# BlueCore_TM_3-Multuimedia.net
KiCad netlist of a schematic drawn in EAGLE
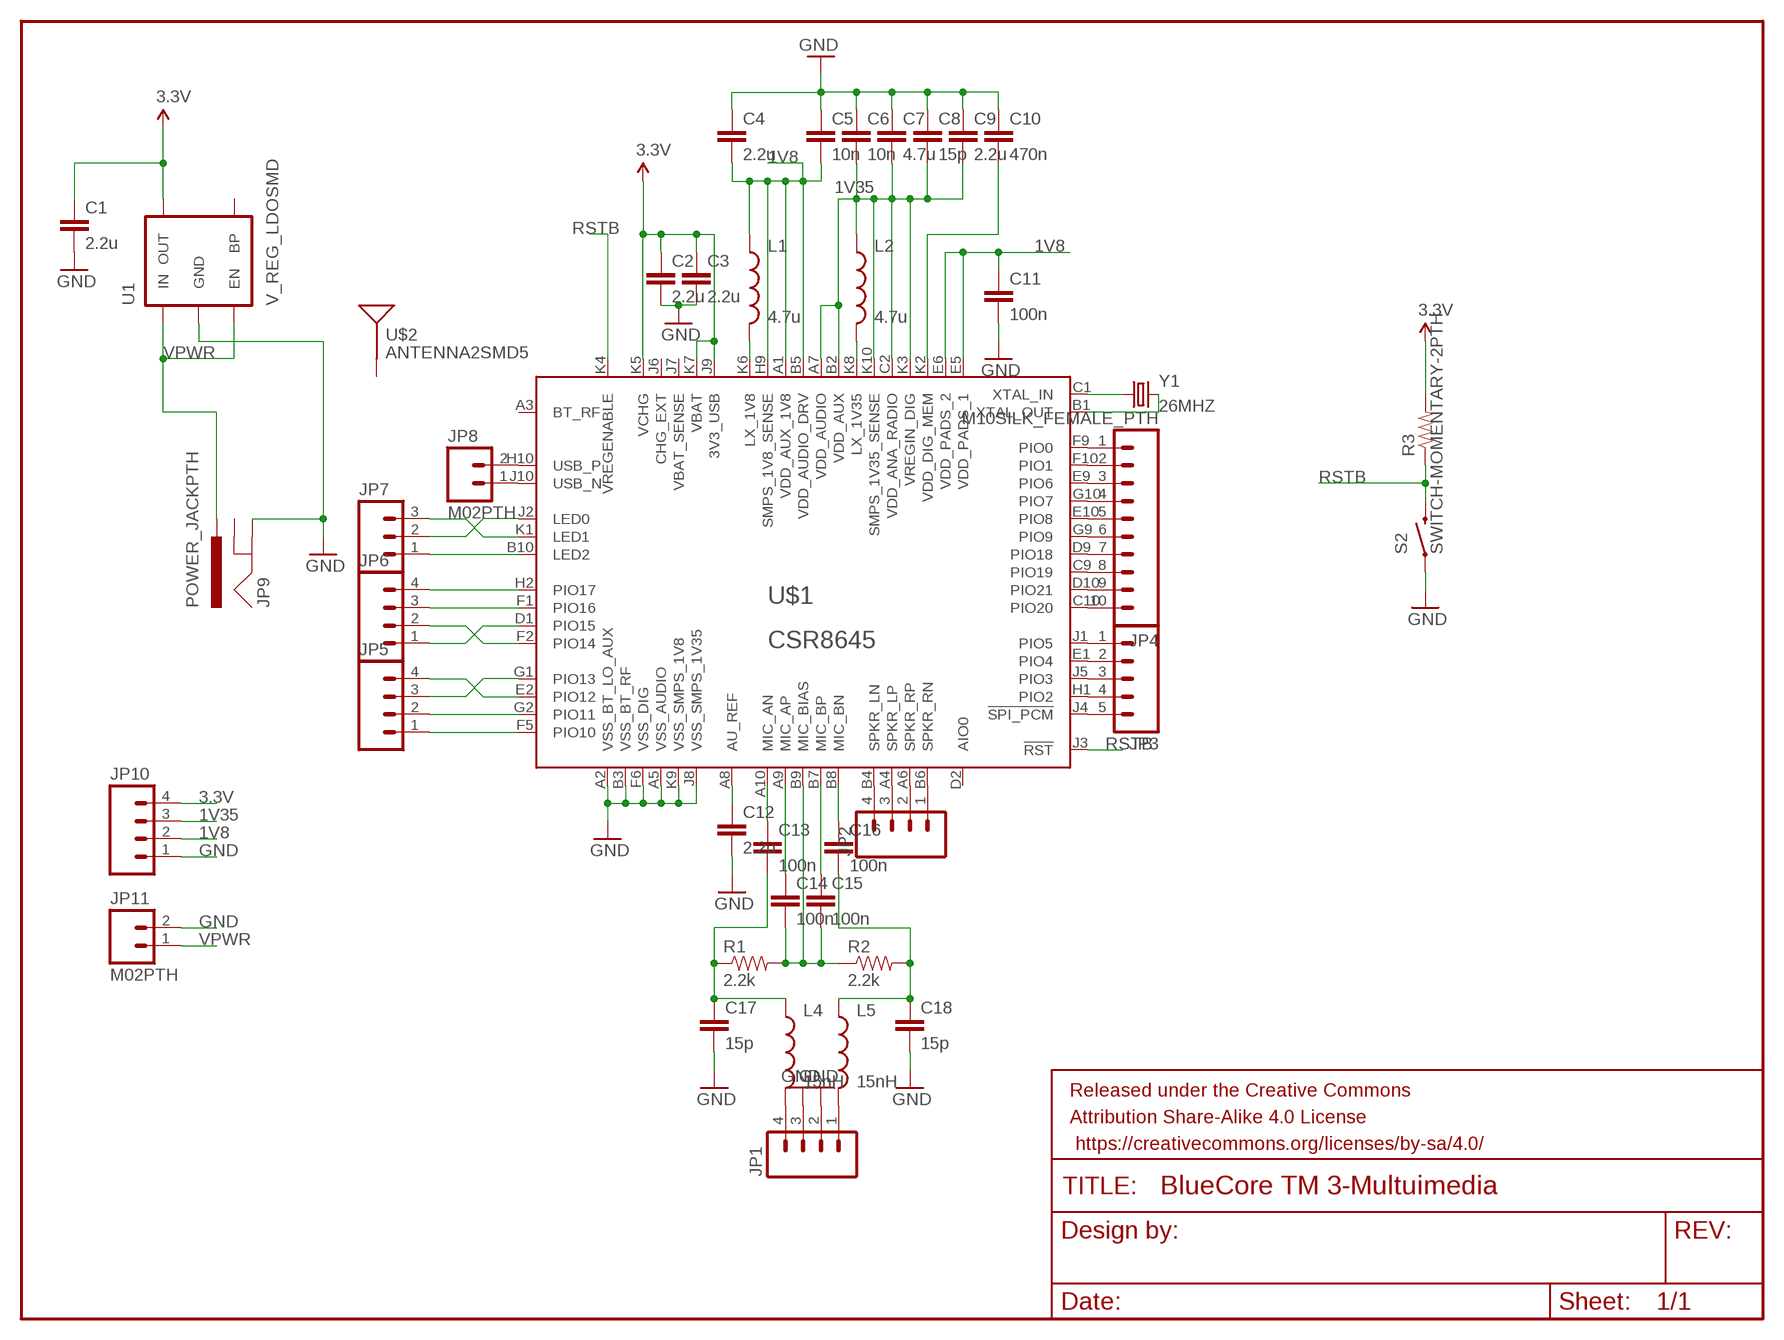
[diagram p0: schematic, sheet 1]

(export (version "E")
  (design (tool "Eeschema 10.0.6"))
  (components
    (comp (ref "C1")
      (value "2.2u")
      (footprint "eagle-import:CAP-PTH-SMALL")
      (libsource (lib "eagle-import") (part "CAPPTH"))
    )
    (comp (ref "C2")
      (value "2.2u")
      (footprint "eagle-import:CAP-PTH-SMALL")
      (libsource (lib "eagle-import") (part "CAPPTH"))
    )
    (comp (ref "C3")
      (value "2.2u")
      (footprint "eagle-import:CAP-PTH-SMALL")
      (libsource (lib "eagle-import") (part "CAPPTH"))
    )
    (comp (ref "C4")
      (value "2.2u")
      (footprint "eagle-import:CAP-PTH-SMALL")
      (libsource (lib "eagle-import") (part "CAPPTH"))
    )
    (comp (ref "C5")
      (value "10n")
      (footprint "eagle-import:CAP-PTH-SMALL")
      (libsource (lib "eagle-import") (part "CAPPTH"))
    )
    (comp (ref "C6")
      (value "10n")
      (footprint "eagle-import:CAP-PTH-SMALL")
      (libsource (lib "eagle-import") (part "CAPPTH"))
    )
    (comp (ref "C7")
      (value "4.7u")
      (footprint "eagle-import:CAP-PTH-SMALL")
      (libsource (lib "eagle-import") (part "CAPPTH"))
    )
    (comp (ref "C8")
      (value "15p")
      (footprint "eagle-import:CAP-PTH-SMALL")
      (libsource (lib "eagle-import") (part "CAPPTH"))
    )
    (comp (ref "C9")
      (value "2.2u")
      (footprint "eagle-import:CAP-PTH-SMALL")
      (libsource (lib "eagle-import") (part "CAPPTH"))
    )
    (comp (ref "C10")
      (value "470n")
      (footprint "eagle-import:CAP-PTH-SMALL")
      (libsource (lib "eagle-import") (part "CAPPTH"))
    )
    (comp (ref "C11")
      (value "100n")
      (footprint "eagle-import:CAP-PTH-SMALL")
      (libsource (lib "eagle-import") (part "CAPPTH"))
    )
    (comp (ref "C12")
      (value "2.2u")
      (footprint "eagle-import:CAP-PTH-SMALL")
      (libsource (lib "eagle-import") (part "CAPPTH"))
    )
    (comp (ref "C13")
      (value "100n")
      (footprint "eagle-import:CAP-PTH-SMALL")
      (libsource (lib "eagle-import") (part "CAPPTH"))
    )
    (comp (ref "C14")
      (value "100n")
      (footprint "eagle-import:CAP-PTH-SMALL")
      (libsource (lib "eagle-import") (part "CAPPTH"))
    )
    (comp (ref "C15")
      (value "100n")
      (footprint "eagle-import:CAP-PTH-SMALL")
      (libsource (lib "eagle-import") (part "CAPPTH"))
    )
    (comp (ref "C16")
      (value "100n")
      (footprint "eagle-import:CAP-PTH-SMALL")
      (libsource (lib "eagle-import") (part "CAPPTH"))
    )
    (comp (ref "C17")
      (value "15p")
      (footprint "eagle-import:CAP-PTH-SMALL")
      (libsource (lib "eagle-import") (part "CAPPTH"))
    )
    (comp (ref "C18")
      (value "15p")
      (footprint "eagle-import:CAP-PTH-SMALL")
      (libsource (lib "eagle-import") (part "CAPPTH"))
    )
    (comp (ref "FRAME1")
      (value "FRAME-LETTER")
      (footprint "eagle-import:CREATIVE_COMMONS")
      (libsource (lib "eagle-import") (part "FRAME-LETTER"))
    )
    (comp (ref "JP1")
      (value "M04PTH")
      (footprint "eagle-import:1X04")
      (libsource (lib "eagle-import") (part "M04PTH"))
    )
    (comp (ref "JP2")
      (value "M04PTH")
      (footprint "eagle-import:1X04")
      (libsource (lib "eagle-import") (part "M04PTH"))
    )
    (comp (ref "JP3")
      (value "M05PTH")
      (footprint "eagle-import:1X05")
      (libsource (lib "eagle-import") (part "M05PTH"))
    )
    (comp (ref "JP4")
      (value "M10SILK_FEMALE_PTH")
      (footprint "eagle-import:1X10")
      (libsource (lib "eagle-import") (part "M10SILK_FEMALE_PTH"))
    )
    (comp (ref "JP5")
      (value "M04PTH")
      (footprint "eagle-import:1X04")
      (libsource (lib "eagle-import") (part "M04PTH"))
    )
    (comp (ref "JP6")
      (value "M04PTH")
      (footprint "eagle-import:1X04")
      (libsource (lib "eagle-import") (part "M04PTH"))
    )
    (comp (ref "JP7")
      (value "M03PTH")
      (footprint "eagle-import:1X03")
      (libsource (lib "eagle-import") (part "M03PTH"))
    )
    (comp (ref "JP8")
      (value "M02PTH")
      (footprint "eagle-import:1X02")
      (libsource (lib "eagle-import") (part "M02PTH"))
    )
    (comp (ref "JP9")
      (value "POWER_JACKPTH")
      (footprint "eagle-import:POWER_JACK_PTH")
      (libsource (lib "eagle-import") (part "POWER_JACKPTH"))
    )
    (comp (ref "JP10")
      (value "M04PTH")
      (footprint "eagle-import:1X04")
      (libsource (lib "eagle-import") (part "M04PTH"))
    )
    (comp (ref "JP11")
      (value "M02PTH")
      (footprint "eagle-import:1X02")
      (libsource (lib "eagle-import") (part "M02PTH"))
    )
    (comp (ref "L1")
      (value "4.7u")
      (footprint "eagle-import:0805")
      (libsource (lib "eagle-import") (part "INDUCTOR0805"))
    )
    (comp (ref "L2")
      (value "4.7u")
      (footprint "eagle-import:0805")
      (libsource (lib "eagle-import") (part "INDUCTOR0805"))
    )
    (comp (ref "L4")
      (value "15nH")
      (footprint "eagle-import:0805")
      (libsource (lib "eagle-import") (part "INDUCTOR0805"))
    )
    (comp (ref "L5")
      (value "15nH")
      (footprint "eagle-import:0805")
      (libsource (lib "eagle-import") (part "INDUCTOR0805"))
    )
    (comp (ref "R1")
      (value "2.2k")
      (footprint "eagle-import:0805")
      (libsource (lib "eagle-import") (part "RESISTOR0805-RES"))
    )
    (comp (ref "R2")
      (value "2.2k")
      (footprint "eagle-import:0805")
      (libsource (lib "eagle-import") (part "RESISTOR0805-RES"))
    )
    (comp (ref "R3")
      (value "RESISTOR0805-RES")
      (footprint "eagle-import:0805")
      (libsource (lib "eagle-import") (part "RESISTOR0805-RES"))
    )
    (comp (ref "S2")
      (value "SWITCH-MOMENTARY-2PTH")
      (footprint "eagle-import:TACTILE-PTH")
      (libsource (lib "eagle-import") (part "SWITCH-MOMENTARY-2PTH"))
    )
    (comp (ref "U$1")
      (value "CSR8645")
      (footprint "eagle-import:VFBGA68")
      (libsource (lib "eagle-import") (part "CSR8645"))
    )
    (comp (ref "U$2")
      (value "ANTENNA2SMD5")
      (footprint "eagle-import:ANTENNA-CHIP5")
      (libsource (lib "eagle-import") (part "ANTENNA2SMD5"))
    )
    (comp (ref "U1")
      (value "V_REG_LDOSMD")
      (footprint "eagle-import:SOT23-5")
      (libsource (lib "eagle-import") (part "V_REG_LDOSMD"))
    )
    (comp (ref "Y1")
      (value "26MHZ")
      (footprint "eagle-import:HC49US")
      (libsource (lib "eagle-import") (part "CRYSTALHC49US"))
    )
  )
  (nets
    (net (code "1") (name "/1V8") (class "Default")
      (node (ref "C11") (pin "1") (pinfunction "1_1") (pintype "passive"))
      (node (ref "C4") (pin "2") (pinfunction "2_2") (pintype "passive"))
      (node (ref "C5") (pin "2") (pinfunction "2_2") (pintype "passive"))
      (node (ref "JP10") (pin "2") (pinfunction "2_2") (pintype "passive"))
      (node (ref "L1") (pin "1") (pinfunction "1_1") (pintype "passive"))
      (node (ref "U$1") (pin "A1") (pinfunction "VDD_AUX_1V8_A1") (pintype "bidirectional"))
      (node (ref "U$1") (pin "B5") (pinfunction "VDD_AUDIO_DRV_B5") (pintype "bidirectional"))
      (node (ref "U$1") (pin "E5") (pinfunction "VDD_PADS_1_E5") (pintype "bidirectional"))
      (node (ref "U$1") (pin "E6") (pinfunction "VDD_PADS_2_E6") (pintype "bidirectional"))
      (node (ref "U$1") (pin "H9") (pinfunction "SMPS_1V8_SENSE_H9") (pintype "bidirectional"))
    )
    (net (code "2") (name "/1V35") (class "Default")
      (node (ref "C6") (pin "2") (pinfunction "2_2") (pintype "passive"))
      (node (ref "C7") (pin "2") (pinfunction "2_2") (pintype "passive"))
      (node (ref "C8") (pin "2") (pinfunction "2_2") (pintype "passive"))
      (node (ref "C9") (pin "2") (pinfunction "2_2") (pintype "passive"))
      (node (ref "JP10") (pin "3") (pinfunction "3_3") (pintype "passive"))
      (node (ref "L2") (pin "1") (pinfunction "1_1") (pintype "passive"))
      (node (ref "U$1") (pin "A7") (pinfunction "VDD_AUDIO_A7") (pintype "bidirectional"))
      (node (ref "U$1") (pin "B2") (pinfunction "VDD_AUX_B2") (pintype "bidirectional"))
      (node (ref "U$1") (pin "C2") (pinfunction "VDD_ANA_RADIO_C2") (pintype "bidirectional"))
      (node (ref "U$1") (pin "K10") (pinfunction "SMPS_1V35_SENSE_K10") (pintype "bidirectional"))
      (node (ref "U$1") (pin "K3") (pinfunction "VREGIN_DIG_K3") (pintype "bidirectional"))
    )
    (net (code "3") (name "/RSTB") (class "Default")
      (node (ref "R3") (pin "1") (pinfunction "1_1") (pintype "passive"))
      (node (ref "S2") (pin "3") (pinfunction "2_3") (pintype "passive"))
      (node (ref "U$1") (pin "J3") (pinfunction "~{RST}_J3") (pintype "input"))
      (node (ref "U$1") (pin "K4") (pinfunction "VREGENABLE_K4") (pintype "bidirectional"))
    )
    (net (code "4") (name "/VPWR") (class "Default")
      (node (ref "JP11") (pin "1") (pinfunction "1_1") (pintype "passive"))
      (node (ref "JP9") (pin "PWR") (pinfunction "PWR_PWR") (pintype "bidirectional"))
      (node (ref "U1") (pin "1") (pinfunction "IN_1") (pintype "input"))
      (node (ref "U1") (pin "3") (pinfunction "EN_3") (pintype "input"))
    )
    (net (code "5") (name "3.3V") (class "Default")
      (node (ref "C1") (pin "1") (pinfunction "1_1") (pintype "passive"))
      (node (ref "C2") (pin "1") (pinfunction "1_1") (pintype "passive"))
      (node (ref "C3") (pin "1") (pinfunction "1_1") (pintype "passive"))
      (node (ref "JP10") (pin "4") (pinfunction "4_4") (pintype "passive"))
      (node (ref "R3") (pin "2") (pinfunction "2_2") (pintype "passive"))
      (node (ref "U$1") (pin "J9") (pinfunction "3V3_USB_J9") (pintype "power_in"))
      (node (ref "U$1") (pin "K5") (pinfunction "VCHG_K5") (pintype "power_in"))
      (node (ref "U$1") (pin "K7") (pinfunction "VBAT_K7") (pintype "power_in"))
      (node (ref "U1") (pin "5") (pinfunction "OUT_5") (pintype "passive"))
    )
    (net (code "6") (name "GND") (class "Default")
      (node (ref "C1") (pin "2") (pinfunction "2_2") (pintype "passive"))
      (node (ref "C10") (pin "1") (pinfunction "1_1") (pintype "passive"))
      (node (ref "C11") (pin "2") (pinfunction "2_2") (pintype "passive"))
      (node (ref "C12") (pin "2") (pinfunction "2_2") (pintype "passive"))
      (node (ref "C17") (pin "2") (pinfunction "2_2") (pintype "passive"))
      (node (ref "C18") (pin "2") (pinfunction "2_2") (pintype "passive"))
      (node (ref "C2") (pin "2") (pinfunction "2_2") (pintype "passive"))
      (node (ref "C3") (pin "2") (pinfunction "2_2") (pintype "passive"))
      (node (ref "C4") (pin "1") (pinfunction "1_1") (pintype "passive"))
      (node (ref "C5") (pin "1") (pinfunction "1_1") (pintype "passive"))
      (node (ref "C6") (pin "1") (pinfunction "1_1") (pintype "passive"))
      (node (ref "C7") (pin "1") (pinfunction "1_1") (pintype "passive"))
      (node (ref "C8") (pin "1") (pinfunction "1_1") (pintype "passive"))
      (node (ref "C9") (pin "1") (pinfunction "1_1") (pintype "passive"))
      (node (ref "JP1") (pin "2") (pinfunction "2_2") (pintype "passive"))
      (node (ref "JP1") (pin "3") (pinfunction "3_3") (pintype "passive"))
      (node (ref "JP10") (pin "1") (pinfunction "1_1") (pintype "passive"))
      (node (ref "JP11") (pin "2") (pinfunction "2_2") (pintype "passive"))
      (node (ref "JP9") (pin "GND") (pinfunction "GND_GND") (pintype "bidirectional"))
      (node (ref "S2") (pin "1") (pinfunction "1_1") (pintype "passive"))
      (node (ref "U$1") (pin "A2") (pinfunction "VSS_BT_LO_AUX_A2") (pintype "bidirectional"))
      (node (ref "U$1") (pin "A5") (pinfunction "VSS_AUDIO_A5") (pintype "bidirectional"))
      (node (ref "U$1") (pin "B3") (pinfunction "VSS_BT_RF_B3") (pintype "bidirectional"))
      (node (ref "U$1") (pin "F6") (pinfunction "VSS_DIG_F6") (pintype "bidirectional"))
      (node (ref "U$1") (pin "J8") (pinfunction "VSS_SMPS_1V35_J8") (pintype "bidirectional"))
      (node (ref "U$1") (pin "K9") (pinfunction "VSS_SMPS_1V8_K9") (pintype "bidirectional"))
      (node (ref "U1") (pin "2") (pinfunction "GND_2") (pintype "input"))
    )
    (net (code "7") (name "Net-(C13-Pad2)") (class "Default")
      (node (ref "C13") (pin "2") (pinfunction "2_2") (pintype "passive"))
      (node (ref "C17") (pin "1") (pinfunction "1_1") (pintype "passive"))
      (node (ref "L4") (pin "1") (pinfunction "1_1") (pintype "passive"))
      (node (ref "R1") (pin "1") (pinfunction "1_1") (pintype "passive"))
    )
    (net (code "8") (name "Net-(C16-Pad2)") (class "Default")
      (node (ref "C16") (pin "2") (pinfunction "2_2") (pintype "passive"))
      (node (ref "C18") (pin "1") (pinfunction "1_1") (pintype "passive"))
      (node (ref "L5") (pin "1") (pinfunction "1_1") (pintype "passive"))
      (node (ref "R2") (pin "2") (pinfunction "2_2") (pintype "passive"))
    )
    (net (code "9") (name "Net-(JP1-Pad1)") (class "Default")
      (node (ref "JP1") (pin "1") (pinfunction "1_1") (pintype "passive"))
      (node (ref "L5") (pin "2") (pinfunction "2_2") (pintype "passive"))
    )
    (net (code "10") (name "Net-(JP1-Pad4)") (class "Default")
      (node (ref "JP1") (pin "4") (pinfunction "4_4") (pintype "passive"))
      (node (ref "L4") (pin "2") (pinfunction "2_2") (pintype "passive"))
    )
    (net (code "11") (name "Net-(U$1-AU_REF)") (class "Default")
      (node (ref "C12") (pin "1") (pinfunction "1_1") (pintype "passive"))
      (node (ref "U$1") (pin "A8") (pinfunction "AU_REF_A8") (pintype "input"))
    )
    (net (code "12") (name "Net-(U$1-LED0)") (class "Default")
      (node (ref "JP7") (pin "2") (pinfunction "2_2") (pintype "passive"))
      (node (ref "U$1") (pin "J2") (pinfunction "LED0_J2") (pintype "bidirectional"))
    )
    (net (code "13") (name "Net-(U$1-LED1)") (class "Default")
      (node (ref "JP7") (pin "3") (pinfunction "3_3") (pintype "passive"))
      (node (ref "U$1") (pin "K1") (pinfunction "LED1_K1") (pintype "bidirectional"))
    )
    (net (code "14") (name "Net-(U$1-LED2)") (class "Default")
      (node (ref "JP7") (pin "1") (pinfunction "1_1") (pintype "passive"))
      (node (ref "U$1") (pin "B10") (pinfunction "LED2_B10") (pintype "bidirectional"))
    )
    (net (code "15") (name "Net-(U$1-LX_1V8)") (class "Default")
      (node (ref "L1") (pin "2") (pinfunction "2_2") (pintype "passive"))
      (node (ref "U$1") (pin "K6") (pinfunction "LX_1V8_K6") (pintype "bidirectional"))
    )
    (net (code "16") (name "Net-(U$1-LX_1V35)") (class "Default")
      (node (ref "L2") (pin "2") (pinfunction "2_2") (pintype "passive"))
      (node (ref "U$1") (pin "K8") (pinfunction "LX_1V35_K8") (pintype "bidirectional"))
    )
    (net (code "17") (name "Net-(U$1-MIC_AN)") (class "Default")
      (node (ref "C13") (pin "1") (pinfunction "1_1") (pintype "passive"))
      (node (ref "U$1") (pin "A10") (pinfunction "MIC_AN_A10") (pintype "input"))
    )
    (net (code "18") (name "Net-(U$1-MIC_AP)") (class "Default")
      (node (ref "C14") (pin "1") (pinfunction "1_1") (pintype "passive"))
      (node (ref "U$1") (pin "A9") (pinfunction "MIC_AP_A9") (pintype "input"))
    )
    (net (code "19") (name "Net-(U$1-MIC_BIAS)") (class "Default")
      (node (ref "C14") (pin "2") (pinfunction "2_2") (pintype "passive"))
      (node (ref "C15") (pin "2") (pinfunction "2_2") (pintype "passive"))
      (node (ref "R1") (pin "2") (pinfunction "2_2") (pintype "passive"))
      (node (ref "R2") (pin "1") (pinfunction "1_1") (pintype "passive"))
      (node (ref "U$1") (pin "B9") (pinfunction "MIC_BIAS_B9") (pintype "output"))
    )
    (net (code "20") (name "Net-(U$1-MIC_BN)") (class "Default")
      (node (ref "C16") (pin "1") (pinfunction "1_1") (pintype "passive"))
      (node (ref "U$1") (pin "B8") (pinfunction "MIC_BN_B8") (pintype "input"))
    )
    (net (code "21") (name "Net-(U$1-MIC_BP)") (class "Default")
      (node (ref "C15") (pin "1") (pinfunction "1_1") (pintype "passive"))
      (node (ref "U$1") (pin "B7") (pinfunction "MIC_BP_B7") (pintype "input"))
    )
    (net (code "22") (name "Net-(U$1-PIO0)") (class "Default")
      (node (ref "JP4") (pin "1") (pinfunction "1_1") (pintype "passive"))
      (node (ref "U$1") (pin "F9") (pinfunction "PIO0_F9") (pintype "bidirectional"))
    )
    (net (code "23") (name "Net-(U$1-PIO1)") (class "Default")
      (node (ref "JP4") (pin "2") (pinfunction "2_2") (pintype "passive"))
      (node (ref "U$1") (pin "F10") (pinfunction "PIO1_F10") (pintype "bidirectional"))
    )
    (net (code "24") (name "Net-(U$1-PIO2)") (class "Default")
      (node (ref "JP3") (pin "4") (pinfunction "4_4") (pintype "passive"))
      (node (ref "U$1") (pin "H1") (pinfunction "PIO2_H1") (pintype "bidirectional"))
    )
    (net (code "25") (name "Net-(U$1-PIO3)") (class "Default")
      (node (ref "JP3") (pin "3") (pinfunction "3_3") (pintype "passive"))
      (node (ref "U$1") (pin "J5") (pinfunction "PIO3_J5") (pintype "bidirectional"))
    )
    (net (code "26") (name "Net-(U$1-PIO4)") (class "Default")
      (node (ref "JP3") (pin "2") (pinfunction "2_2") (pintype "passive"))
      (node (ref "U$1") (pin "E1") (pinfunction "PIO4_E1") (pintype "bidirectional"))
    )
    (net (code "27") (name "Net-(U$1-PIO5)") (class "Default")
      (node (ref "JP3") (pin "1") (pinfunction "1_1") (pintype "passive"))
      (node (ref "U$1") (pin "J1") (pinfunction "PIO5_J1") (pintype "bidirectional"))
    )
    (net (code "28") (name "Net-(U$1-PIO6)") (class "Default")
      (node (ref "JP4") (pin "3") (pinfunction "3_3") (pintype "passive"))
      (node (ref "U$1") (pin "E9") (pinfunction "PIO6_E9") (pintype "bidirectional"))
    )
    (net (code "29") (name "Net-(U$1-PIO7)") (class "Default")
      (node (ref "JP4") (pin "4") (pinfunction "4_4") (pintype "passive"))
      (node (ref "U$1") (pin "G10") (pinfunction "PIO7_G10") (pintype "bidirectional"))
    )
    (net (code "30") (name "Net-(U$1-PIO8)") (class "Default")
      (node (ref "JP4") (pin "5") (pinfunction "5_5") (pintype "passive"))
      (node (ref "U$1") (pin "E10") (pinfunction "PIO8_E10") (pintype "bidirectional"))
    )
    (net (code "31") (name "Net-(U$1-PIO9)") (class "Default")
      (node (ref "JP4") (pin "6") (pinfunction "6_6") (pintype "passive"))
      (node (ref "U$1") (pin "G9") (pinfunction "PIO9_G9") (pintype "bidirectional"))
    )
    (net (code "32") (name "Net-(U$1-PIO10)") (class "Default")
      (node (ref "JP5") (pin "1") (pinfunction "1_1") (pintype "passive"))
      (node (ref "U$1") (pin "F5") (pinfunction "PIO10_F5") (pintype "bidirectional"))
    )
    (net (code "33") (name "Net-(U$1-PIO11)") (class "Default")
      (node (ref "JP5") (pin "2") (pinfunction "2_2") (pintype "passive"))
      (node (ref "U$1") (pin "G2") (pinfunction "PIO11_G2") (pintype "bidirectional"))
    )
    (net (code "34") (name "Net-(U$1-PIO12)") (class "Default")
      (node (ref "JP5") (pin "4") (pinfunction "4_4") (pintype "passive"))
      (node (ref "U$1") (pin "E2") (pinfunction "PIO12_E2") (pintype "bidirectional"))
    )
    (net (code "35") (name "Net-(U$1-PIO13)") (class "Default")
      (node (ref "JP5") (pin "3") (pinfunction "3_3") (pintype "passive"))
      (node (ref "U$1") (pin "G1") (pinfunction "PIO13_G1") (pintype "bidirectional"))
    )
    (net (code "36") (name "Net-(U$1-PIO14)") (class "Default")
      (node (ref "JP6") (pin "2") (pinfunction "2_2") (pintype "passive"))
      (node (ref "U$1") (pin "F2") (pinfunction "PIO14_F2") (pintype "bidirectional"))
    )
    (net (code "37") (name "Net-(U$1-PIO15)") (class "Default")
      (node (ref "JP6") (pin "1") (pinfunction "1_1") (pintype "passive"))
      (node (ref "U$1") (pin "D1") (pinfunction "PIO15_D1") (pintype "bidirectional"))
    )
    (net (code "38") (name "Net-(U$1-PIO16)") (class "Default")
      (node (ref "JP6") (pin "3") (pinfunction "3_3") (pintype "passive"))
      (node (ref "U$1") (pin "F1") (pinfunction "PIO16_F1") (pintype "bidirectional"))
    )
    (net (code "39") (name "Net-(U$1-PIO17)") (class "Default")
      (node (ref "JP6") (pin "4") (pinfunction "4_4") (pintype "passive"))
      (node (ref "U$1") (pin "H2") (pinfunction "PIO17_H2") (pintype "bidirectional"))
    )
    (net (code "40") (name "Net-(U$1-PIO18)") (class "Default")
      (node (ref "JP4") (pin "7") (pinfunction "7_7") (pintype "passive"))
      (node (ref "U$1") (pin "D9") (pinfunction "PIO18_D9") (pintype "bidirectional"))
    )
    (net (code "41") (name "Net-(U$1-PIO19)") (class "Default")
      (node (ref "JP4") (pin "8") (pinfunction "8_8") (pintype "passive"))
      (node (ref "U$1") (pin "C9") (pinfunction "PIO19_C9") (pintype "bidirectional"))
    )
    (net (code "42") (name "Net-(U$1-PIO20)") (class "Default")
      (node (ref "JP4") (pin "10") (pinfunction "10_10") (pintype "passive"))
      (node (ref "U$1") (pin "C10") (pinfunction "PIO20_C10") (pintype "bidirectional"))
    )
    (net (code "43") (name "Net-(U$1-PIO21)") (class "Default")
      (node (ref "JP4") (pin "9") (pinfunction "9_9") (pintype "passive"))
      (node (ref "U$1") (pin "D10") (pinfunction "PIO21_D10") (pintype "bidirectional"))
    )
    (net (code "44") (name "Net-(U$1-SPKR_LN)") (class "Default")
      (node (ref "JP2") (pin "4") (pinfunction "4_4") (pintype "passive"))
      (node (ref "U$1") (pin "B4") (pinfunction "SPKR_LN_B4") (pintype "output"))
    )
    (net (code "45") (name "Net-(U$1-SPKR_LP)") (class "Default")
      (node (ref "JP2") (pin "3") (pinfunction "3_3") (pintype "passive"))
      (node (ref "U$1") (pin "A4") (pinfunction "SPKR_LP_A4") (pintype "output"))
    )
    (net (code "46") (name "Net-(U$1-SPKR_RN)") (class "Default")
      (node (ref "JP2") (pin "1") (pinfunction "1_1") (pintype "passive"))
      (node (ref "U$1") (pin "B6") (pinfunction "SPKR_RN_B6") (pintype "output"))
    )
    (net (code "47") (name "Net-(U$1-SPKR_RP)") (class "Default")
      (node (ref "JP2") (pin "2") (pinfunction "2_2") (pintype "passive"))
      (node (ref "U$1") (pin "A6") (pinfunction "SPKR_RP_A6") (pintype "output"))
    )
    (net (code "48") (name "Net-(U$1-USB_N)") (class "Default")
      (node (ref "JP8") (pin "1") (pinfunction "1_1") (pintype "passive"))
      (node (ref "U$1") (pin "J10") (pinfunction "USB_N_J10") (pintype "bidirectional"))
    )
    (net (code "49") (name "Net-(U$1-USB_P)") (class "Default")
      (node (ref "JP8") (pin "2") (pinfunction "2_2") (pintype "passive"))
      (node (ref "U$1") (pin "H10") (pinfunction "USB_P_H10") (pintype "bidirectional"))
    )
    (net (code "50") (name "Net-(U$1-VDD_DIG_MEM)") (class "Default")
      (node (ref "C10") (pin "2") (pinfunction "2_2") (pintype "passive"))
      (node (ref "U$1") (pin "K2") (pinfunction "VDD_DIG_MEM_K2") (pintype "bidirectional"))
    )
    (net (code "51") (name "Net-(U$1-XTAL_IN)") (class "Default")
      (node (ref "U$1") (pin "C1") (pinfunction "XTAL_IN_C1") (pintype "input"))
      (node (ref "Y1") (pin "1") (pinfunction "1_1") (pintype "passive"))
    )
    (net (code "52") (name "Net-(U$1-XTAL_OUT)") (class "Default")
      (node (ref "U$1") (pin "B1") (pinfunction "XTAL_OUT_B1") (pintype "bidirectional"))
      (node (ref "Y1") (pin "2") (pinfunction "2_2") (pintype "passive"))
    )
    (net (code "53") (name "Net-(U$1-~{SPI_PCM})") (class "Default")
      (node (ref "JP3") (pin "5") (pinfunction "5_5") (pintype "passive"))
      (node (ref "U$1") (pin "J4") (pinfunction "~{SPI_PCM}_J4") (pintype "input"))
    )
    (net (code "54") (name "unconnected-(JP9-PadGNDBREAK)") (class "Default")
      (node (ref "JP9") (pin "GNDBREAK") (pinfunction "GNDBREAK_GNDBREAK") (pintype "bidirectional"))
    )
    (net (code "55") (name "unconnected-(U$1-AIO0-PadD2)") (class "Default")
      (node (ref "U$1") (pin "D2") (pinfunction "AIO0_D2") (pintype "bidirectional"))
    )
    (net (code "56") (name "unconnected-(U$1-BT_RF-PadA3)") (class "Default")
      (node (ref "U$1") (pin "A3") (pinfunction "BT_RF_A3") (pintype "bidirectional"))
    )
    (net (code "57") (name "unconnected-(U$1-CHG_EXT-PadJ6)") (class "Default")
      (node (ref "U$1") (pin "J6") (pinfunction "CHG_EXT_J6") (pintype "bidirectional"))
    )
    (net (code "58") (name "unconnected-(U$1-VBAT_SENSE-PadJ7)") (class "Default")
      (node (ref "U$1") (pin "J7") (pinfunction "VBAT_SENSE_J7") (pintype "bidirectional"))
    )
    (net (code "59") (name "unconnected-(U$2-SIGNAL-PadFEED)") (class "Default")
      (node (ref "U$2") (pin "FEED") (pinfunction "SIGNAL_FEED") (pintype "bidirectional"))
    )
    (net (code "60") (name "unconnected-(U1-BP-Pad4)") (class "Default")
      (node (ref "U1") (pin "4") (pinfunction "BP_4") (pintype "input"))
    )
  )
)
